# LCLFilter_Updated.net
KiCad netlist of a schematic drawn in Altium Designer
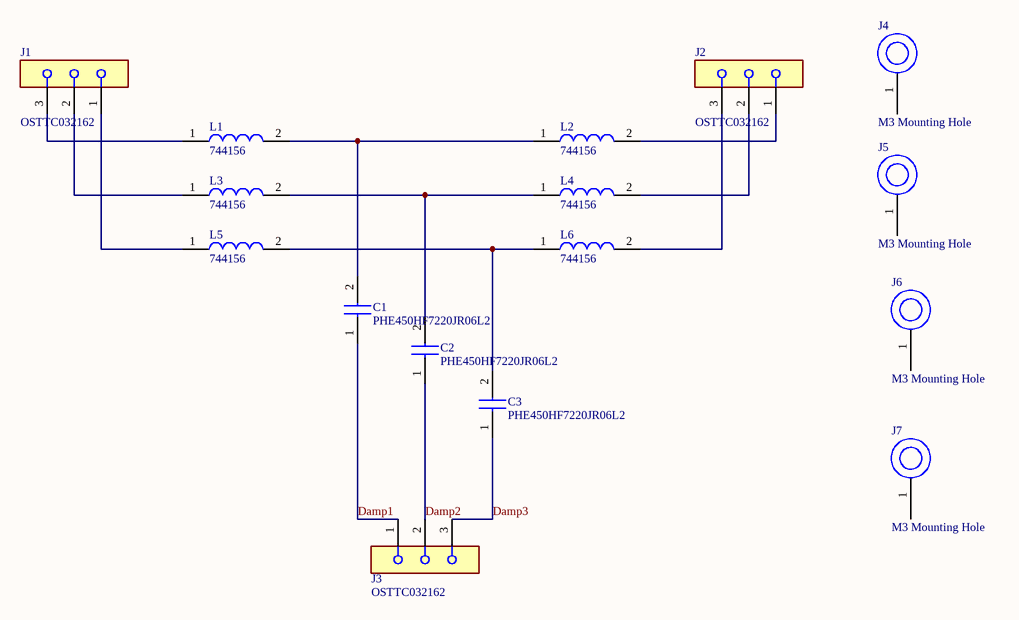
[diagram p0: LCLFilter_Updated.SchDoc]

(export (version "E")
  (design (tool "Eeschema 10.0.6"))
  (components
    (comp (ref "C1")
      (value "PHE450HF7220JR06L2")
      (footprint "Film Capacitor PHE450HF7220JR06L2")
      (description "Capacitor")
      (libsource (lib "FYP_Components") (part "PHE450HF7220JR06L2"))
    )
    (comp (ref "C2")
      (value "PHE450HF7220JR06L2")
      (footprint "Film Capacitor PHE450HF7220JR06L2")
      (description "Capacitor")
      (libsource (lib "FYP_Components") (part "PHE450HF7220JR06L2"))
    )
    (comp (ref "C3")
      (value "PHE450HF7220JR06L2")
      (footprint "Film Capacitor PHE450HF7220JR06L2")
      (description "Capacitor")
      (libsource (lib "FYP_Components") (part "PHE450HF7220JR06L2"))
    )
    (comp (ref "J1")
      (value "3PinTerminal")
      (footprint "3 Pin Terminal")
      (description "3 Position Terminal Block 5.08mm")
      (fields
        (field (name "VOLTAGE") "300V")
        (field (name "MANUFACTURER") "On Shore Technology")
        (field (name "PART NUMBER") "OSTTC032162")
      )
      (libsource (lib "FYP_Components") (part "3PinTerminal"))
    )
    (comp (ref "J2")
      (value "3PinTerminal")
      (footprint "3 Pin Terminal")
      (description "3 Position Terminal Block 5.08mm")
      (fields
        (field (name "VOLTAGE") "300V")
        (field (name "MANUFACTURER") "On Shore Technology")
        (field (name "PART NUMBER") "OSTTC032162")
      )
      (libsource (lib "FYP_Components") (part "3PinTerminal"))
    )
    (comp (ref "J3")
      (value "3PinTerminal")
      (footprint "3 Pin Terminal")
      (description "3 Position Terminal Block 5.08mm")
      (fields
        (field (name "VOLTAGE") "300V")
        (field (name "MANUFACTURER") "On Shore Technology")
        (field (name "PART NUMBER") "OSTTC032162")
      )
      (libsource (lib "") (part "3PinTerminal_1"))
    )
    (comp (ref "J4")
      (value "M3 Mounting Hole")
      (footprint "M3 Mounting Hole")
      (libsource (lib "FYP_Components") (part "M3 Mounting Hole"))
    )
    (comp (ref "J5")
      (value "M3 Mounting Hole")
      (footprint "M3 Mounting Hole")
      (libsource (lib "FYP_Components") (part "M3 Mounting Hole"))
    )
    (comp (ref "J6")
      (value "M3 Mounting Hole")
      (footprint "M3 Mounting Hole")
      (libsource (lib "FYP_Components") (part "M3 Mounting Hole"))
    )
    (comp (ref "J7")
      (value "M3 Mounting Hole")
      (footprint "M3 Mounting Hole")
      (libsource (lib "FYP_Components") (part "M3 Mounting Hole"))
    )
    (comp (ref "L1")
      (value "744156")
      (footprint "Toroid Inductor 744156")
      (description "Toroidal Inductor, WE-SI, 380 µH, 6.2 A, 0.07 ohm, ± 20%")
      (libsource (lib "FYP_Components") (part "744156"))
    )
    (comp (ref "L2")
      (value "744156")
      (footprint "Toroid Inductor 744156")
      (description "Toroidal Inductor, WE-SI, 380 µH, 6.2 A, 0.07 ohm, ± 20%")
      (libsource (lib "FYP_Components") (part "744156"))
    )
    (comp (ref "L3")
      (value "744156")
      (footprint "Toroid Inductor 744156")
      (description "Toroidal Inductor, WE-SI, 380 µH, 6.2 A, 0.07 ohm, ± 20%")
      (libsource (lib "FYP_Components") (part "744156"))
    )
    (comp (ref "L4")
      (value "744156")
      (footprint "Toroid Inductor 744156")
      (description "Toroidal Inductor, WE-SI, 380 µH, 6.2 A, 0.07 ohm, ± 20%")
      (libsource (lib "FYP_Components") (part "744156"))
    )
    (comp (ref "L5")
      (value "744156")
      (footprint "Toroid Inductor 744156")
      (description "Toroidal Inductor, WE-SI, 380 µH, 6.2 A, 0.07 ohm, ± 20%")
      (libsource (lib "FYP_Components") (part "744156"))
    )
    (comp (ref "L6")
      (value "744156")
      (footprint "Toroid Inductor 744156")
      (description "Toroidal Inductor, WE-SI, 380 µH, 6.2 A, 0.07 ohm, ± 20%")
      (libsource (lib "FYP_Components") (part "744156"))
    )
  )
  (nets
    (net (code "1") (name "/Damp1") (class "Default")
      (node (ref "C1") (pin "1") (pinfunction "1_1") (pintype "passive"))
      (node (ref "J3") (pin "1") (pinfunction "1_1") (pintype "passive"))
    )
    (net (code "2") (name "/Damp2") (class "Default")
      (node (ref "C2") (pin "1") (pinfunction "1_1") (pintype "passive"))
      (node (ref "J3") (pin "2") (pinfunction "2_2") (pintype "passive"))
    )
    (net (code "3") (name "/Damp3") (class "Default")
      (node (ref "C3") (pin "1") (pinfunction "1_1") (pintype "passive"))
      (node (ref "J3") (pin "3") (pinfunction "3_3") (pintype "passive"))
    )
    (net (code "4") (name "Net-(C1-Pad2)") (class "Default")
      (node (ref "C1") (pin "2") (pinfunction "2_2") (pintype "passive"))
      (node (ref "L1") (pin "2") (pinfunction "2_2") (pintype "passive"))
      (node (ref "L2") (pin "1") (pinfunction "1_1") (pintype "passive"))
    )
    (net (code "5") (name "Net-(C2-Pad2)") (class "Default")
      (node (ref "C2") (pin "2") (pinfunction "2_2") (pintype "passive"))
      (node (ref "L3") (pin "2") (pinfunction "2_2") (pintype "passive"))
      (node (ref "L4") (pin "1") (pinfunction "1_1") (pintype "passive"))
    )
    (net (code "6") (name "Net-(C3-Pad2)") (class "Default")
      (node (ref "C3") (pin "2") (pinfunction "2_2") (pintype "passive"))
      (node (ref "L5") (pin "2") (pinfunction "2_2") (pintype "passive"))
      (node (ref "L6") (pin "1") (pinfunction "1_1") (pintype "passive"))
    )
    (net (code "7") (name "Net-(J1-Pad1)") (class "Default")
      (node (ref "J1") (pin "1") (pinfunction "1_1") (pintype "passive"))
      (node (ref "L5") (pin "1") (pinfunction "1_1") (pintype "passive"))
    )
    (net (code "8") (name "Net-(J1-Pad2)") (class "Default")
      (node (ref "J1") (pin "2") (pinfunction "2_2") (pintype "passive"))
      (node (ref "L3") (pin "1") (pinfunction "1_1") (pintype "passive"))
    )
    (net (code "9") (name "Net-(J1-Pad3)") (class "Default")
      (node (ref "J1") (pin "3") (pinfunction "3_3") (pintype "passive"))
      (node (ref "L1") (pin "1") (pinfunction "1_1") (pintype "passive"))
    )
    (net (code "10") (name "Net-(J2-Pad1)") (class "Default")
      (node (ref "J2") (pin "1") (pinfunction "1_1") (pintype "passive"))
      (node (ref "L2") (pin "2") (pinfunction "2_2") (pintype "passive"))
    )
    (net (code "11") (name "Net-(J2-Pad2)") (class "Default")
      (node (ref "J2") (pin "2") (pinfunction "2_2") (pintype "passive"))
      (node (ref "L4") (pin "2") (pinfunction "2_2") (pintype "passive"))
    )
    (net (code "12") (name "Net-(J2-Pad3)") (class "Default")
      (node (ref "J2") (pin "3") (pinfunction "3_3") (pintype "passive"))
      (node (ref "L6") (pin "2") (pinfunction "2_2") (pintype "passive"))
    )
    (net (code "13") (name "unconnected-(J4-Pad1)") (class "Default")
      (node (ref "J4") (pin "1") (pinfunction "1_1") (pintype "passive"))
    )
    (net (code "14") (name "unconnected-(J5-Pad1)") (class "Default")
      (node (ref "J5") (pin "1") (pinfunction "1_1") (pintype "passive"))
    )
    (net (code "15") (name "unconnected-(J6-Pad1)") (class "Default")
      (node (ref "J6") (pin "1") (pinfunction "1_1") (pintype "passive"))
    )
    (net (code "16") (name "unconnected-(J7-Pad1)") (class "Default")
      (node (ref "J7") (pin "1") (pinfunction "1_1") (pintype "passive"))
    )
  )
)
